# Urukul_FPGA.net
KiCad netlist of a schematic drawn in Altium Designer
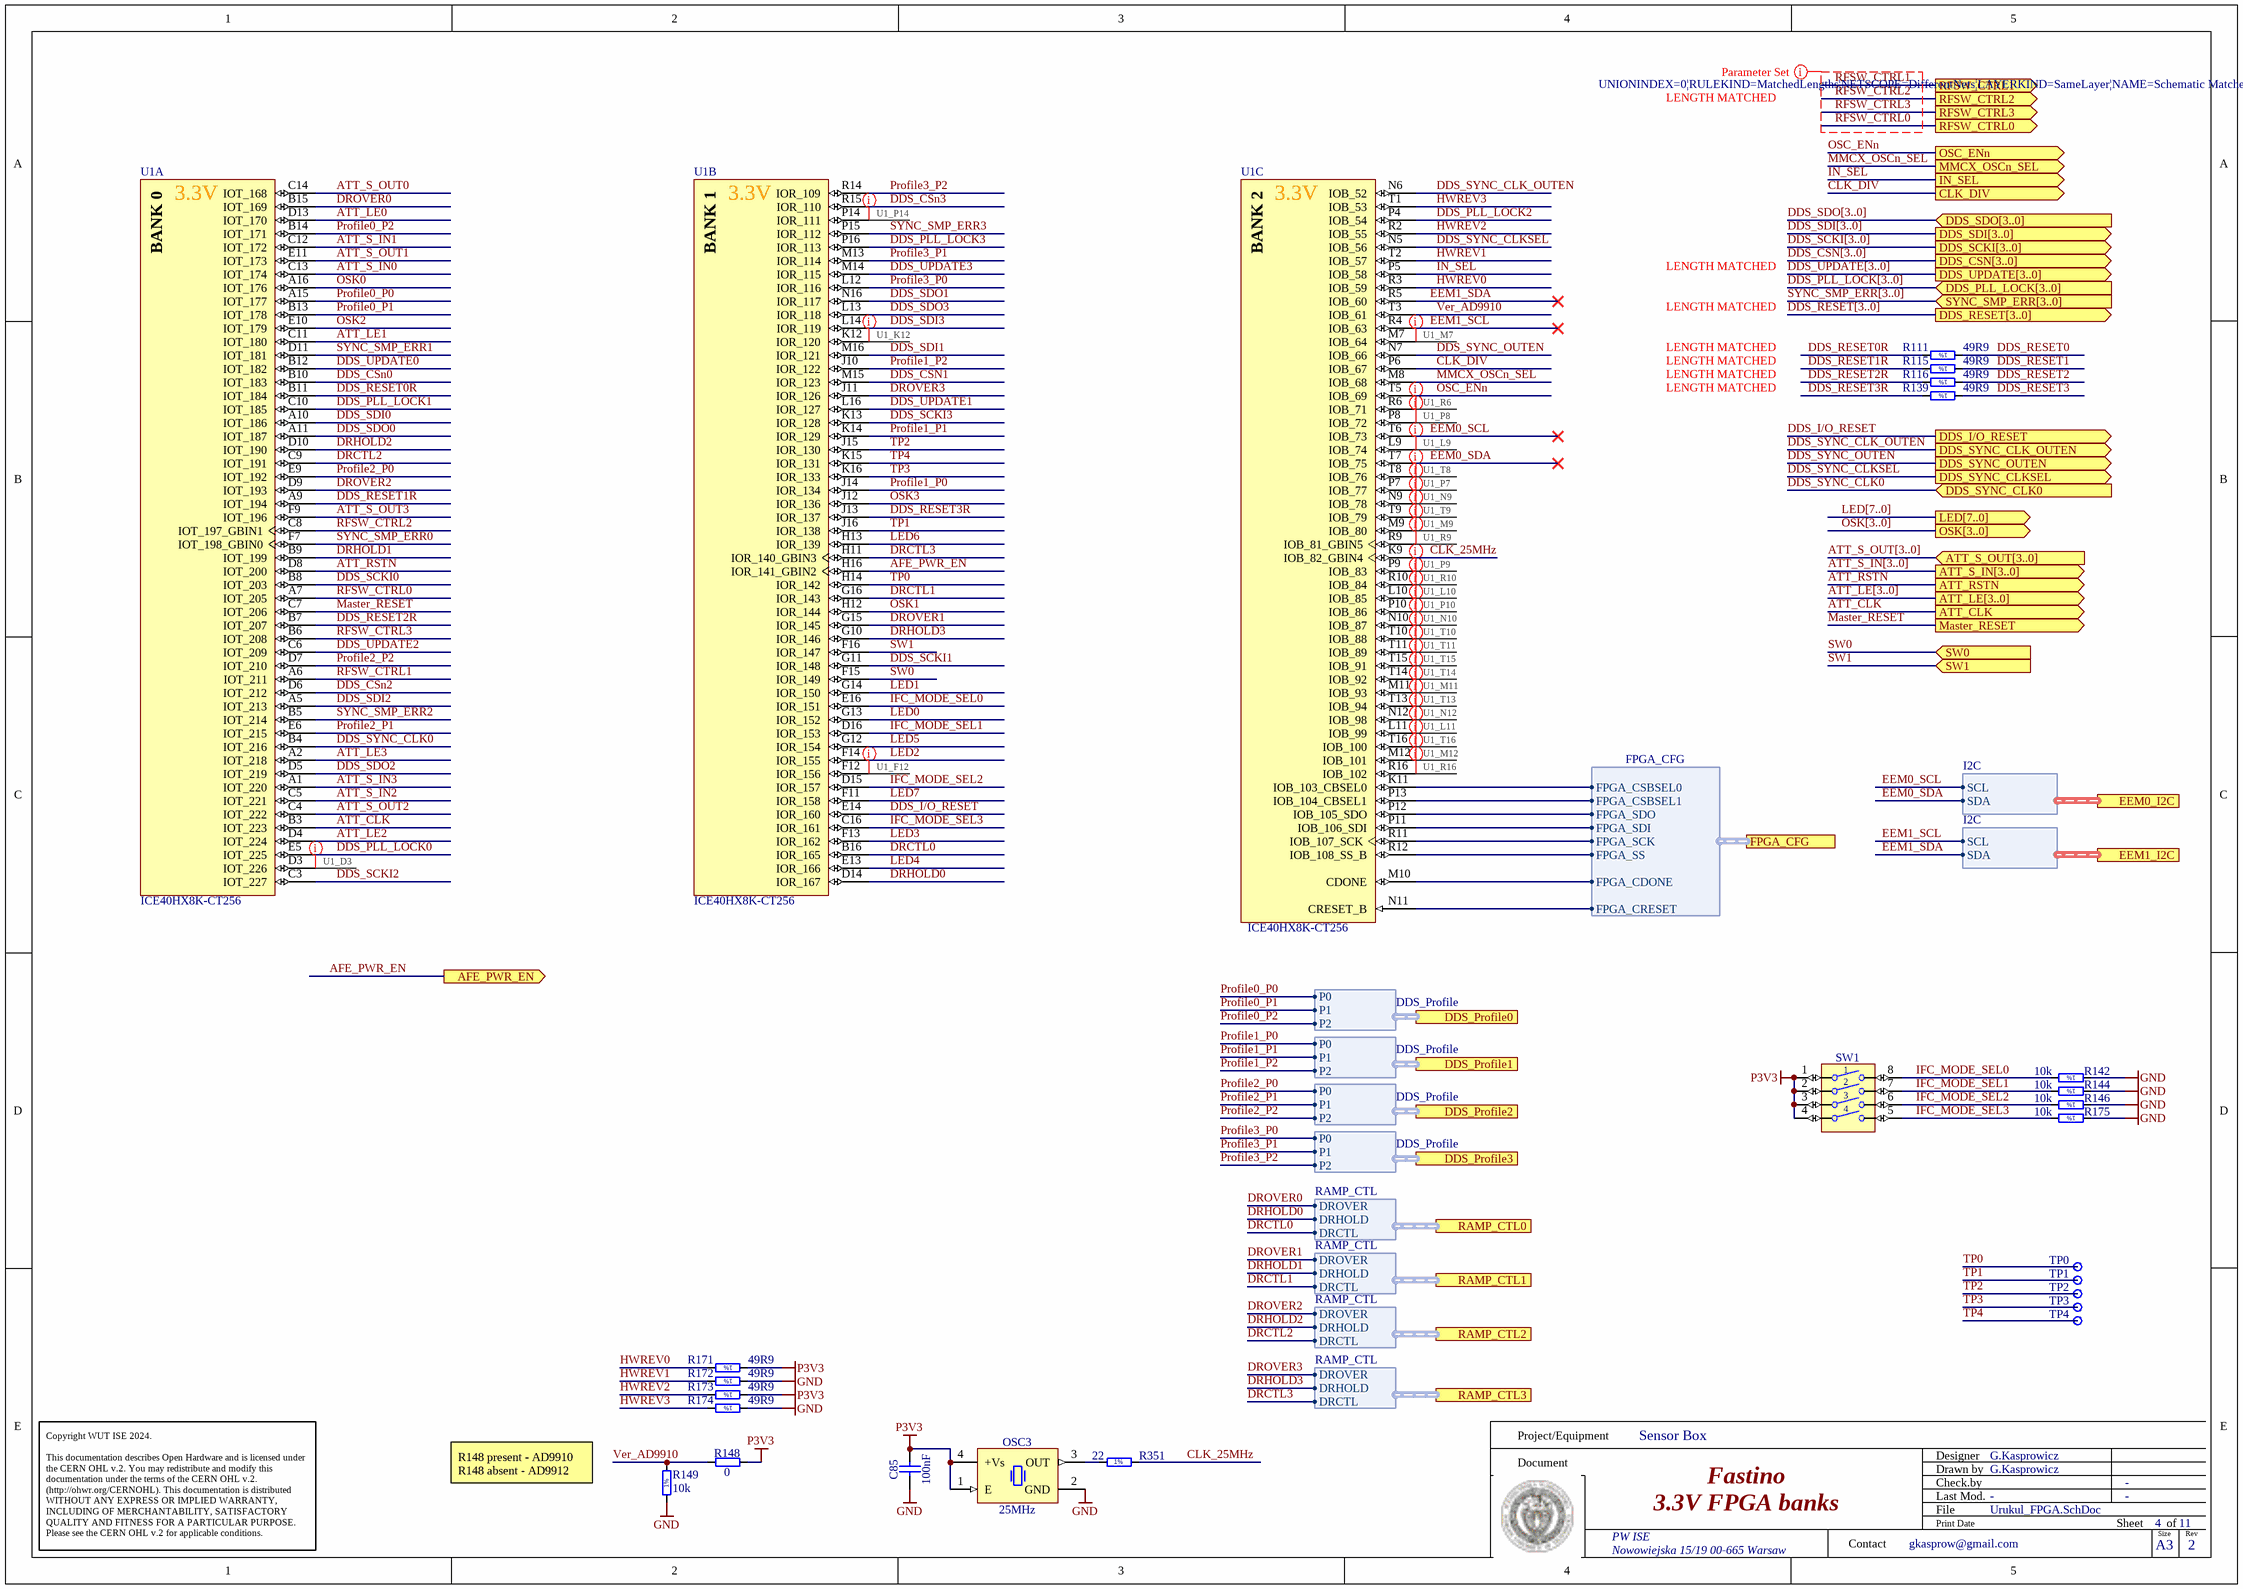
[diagram p0: Urukul_FPGA.SchDoc]

(export (version "E")
  (design (tool "Eeschema 10.0.6"))
  (components
    (comp (ref "C85")
      (value "100nF")
      (footprint "CAPC1005X55N")
      (description "Non-polarised capacitor")
      (fields
        (field (name "PART NUMBER") "CC0402_100NF_16V_10%_X5R")
        (field (name "VOLTAGE") "16V")
        (field (name "AUTHOR") "CERN DEM JLC")
      )
      (libsource (lib "Capacitors") (part "Capacitor - non polarized"))
    )
    (comp (ref "OSC3")
      (value "25MHz")
      (footprint "OSC_IQD_CFPS-39")
      (description "Oscillator 4 pins 1=E 2=GND 3=OUT 4=+Vs")
      (fields
        (field (name "PART NUMBER") "OSC_25MHZ_IQD_LFSPXO025165")
        (field (name "MANUFACTURER") "IQD FREQUENCY PRODUCTS")
        (field (name "AUTHOR") "CERN DEM JLC")
      )
      (libsource (lib "ICs And Semiconductors") (part "Oscillator 1E 2GND 3OUT 4Vs"))
    )
    (comp (ref "R111")
      (value "49R9")
      (footprint "RESC1005X40N")
      (description "Resistor - 1%")
      (fields
        (field (name "PART NUMBER") "R0402_49R9_1%_0.0625W_100PPM")
        (field (name "POWER") "0.0625W")
        (field (name "AUTHOR") "CERN DEM JLC")
      )
      (libsource (lib "Resistors") (part "Resistor - 1%"))
    )
    (comp (ref "R115")
      (value "49R9")
      (footprint "RESC1005X40N")
      (description "Resistor - 1%")
      (fields
        (field (name "PART NUMBER") "R0402_49R9_1%_0.0625W_100PPM")
        (field (name "POWER") "0.0625W")
        (field (name "AUTHOR") "CERN DEM JLC")
      )
      (libsource (lib "Resistors") (part "Resistor - 1%"))
    )
    (comp (ref "R116")
      (value "49R9")
      (footprint "RESC1005X40N")
      (description "Resistor - 1%")
      (fields
        (field (name "PART NUMBER") "R0402_49R9_1%_0.0625W_100PPM")
        (field (name "POWER") "0.0625W")
        (field (name "AUTHOR") "CERN DEM JLC")
      )
      (libsource (lib "Resistors") (part "Resistor - 1%"))
    )
    (comp (ref "R139")
      (value "49R9")
      (footprint "RESC1005X40N")
      (description "Resistor - 1%")
      (fields
        (field (name "PART NUMBER") "R0402_49R9_1%_0.0625W_100PPM")
        (field (name "POWER") "0.0625W")
        (field (name "AUTHOR") "CERN DEM JLC")
      )
      (libsource (lib "Resistors") (part "Resistor - 1%"))
    )
    (comp (ref "R142")
      (value "10k")
      (footprint "RESC1005X40N")
      (description "Resistor - 1%")
      (fields
        (field (name "PART NUMBER") "R0402_10K_1%_0.0625W_100PPM")
        (field (name "POWER") "0.0625W")
        (field (name "AUTHOR") "CERN DEM JLC")
      )
      (libsource (lib "Resistors") (part "Resistor - 1%"))
    )
    (comp (ref "R144")
      (value "10k")
      (footprint "RESC1005X40N")
      (description "Resistor - 1%")
      (fields
        (field (name "PART NUMBER") "R0402_10K_1%_0.0625W_100PPM")
        (field (name "POWER") "0.0625W")
        (field (name "AUTHOR") "CERN DEM JLC")
      )
      (libsource (lib "Resistors") (part "Resistor - 1%"))
    )
    (comp (ref "R146")
      (value "10k")
      (footprint "RESC1005X40N")
      (description "Resistor - 1%")
      (fields
        (field (name "PART NUMBER") "R0402_10K_1%_0.0625W_100PPM")
        (field (name "POWER") "0.0625W")
        (field (name "AUTHOR") "CERN DEM JLC")
      )
      (libsource (lib "Resistors") (part "Resistor - 1%"))
    )
    (comp (ref "R148")
      (value "0")
      (footprint "RESC1005X40N")
      (description "Resistor")
      (fields
        (field (name "PART NUMBER") "R0402_0R_JUMPER")
        (field (name "MANUFACTURER") "GENERIC")
        (field (name "AUTHOR") "CERN DEM JLC")
      )
      (libsource (lib "Resistors") (part "Resistor"))
    )
    (comp (ref "R149")
      (value "10k")
      (footprint "RESC1005X40N")
      (description "Resistor - 1%")
      (fields
        (field (name "PART NUMBER") "R0402_10K_1%_0.0625W_100PPM")
        (field (name "POWER") "0.0625W")
        (field (name "AUTHOR") "CERN DEM JLC")
      )
      (libsource (lib "Resistors") (part "Resistor - 1%"))
    )
    (comp (ref "R171")
      (value "49R9")
      (footprint "RESC1005X40N")
      (description "Resistor - 1%")
      (fields
        (field (name "PART NUMBER") "R0402_49R9_1%_0.0625W_100PPM")
        (field (name "POWER") "0.0625W")
        (field (name "AUTHOR") "CERN DEM JLC")
      )
      (libsource (lib "Resistors") (part "Resistor - 1%"))
    )
    (comp (ref "R172")
      (value "49R9")
      (footprint "RESC1005X40N")
      (description "Resistor - 1%")
      (fields
        (field (name "PART NUMBER") "R0402_49R9_1%_0.0625W_100PPM")
        (field (name "POWER") "0.0625W")
        (field (name "AUTHOR") "CERN DEM JLC")
      )
      (libsource (lib "Resistors") (part "Resistor - 1%"))
    )
    (comp (ref "R173")
      (value "49R9")
      (footprint "RESC1005X40N")
      (description "Resistor - 1%")
      (fields
        (field (name "PART NUMBER") "R0402_49R9_1%_0.0625W_100PPM")
        (field (name "POWER") "0.0625W")
        (field (name "AUTHOR") "CERN DEM JLC")
      )
      (libsource (lib "Resistors") (part "Resistor - 1%"))
    )
    (comp (ref "R174")
      (value "49R9")
      (footprint "RESC1005X40N")
      (description "Resistor - 1%")
      (fields
        (field (name "PART NUMBER") "R0402_49R9_1%_0.0625W_100PPM")
        (field (name "POWER") "0.0625W")
        (field (name "AUTHOR") "CERN DEM JLC")
      )
      (libsource (lib "Resistors") (part "Resistor - 1%"))
    )
    (comp (ref "R175")
      (value "10k")
      (footprint "RESC1005X40N")
      (description "Resistor - 1%")
      (fields
        (field (name "PART NUMBER") "R0402_10K_1%_0.0625W_100PPM")
        (field (name "POWER") "0.0625W")
        (field (name "AUTHOR") "CERN DEM JLC")
      )
      (libsource (lib "Resistors") (part "Resistor - 1%"))
    )
    (comp (ref "R351")
      (value "22")
      (footprint "RESC1005X40N")
      (description "Resistor - 1%")
      (fields
        (field (name "PART NUMBER") "R0402_22R_1%_0.0625W_100PPM")
        (field (name "POWER") "0.0625W")
        (field (name "AUTHOR") "CERN DEM JLC")
      )
      (libsource (lib "Resistors") (part "Resistor - 1%"))
    )
    (comp (ref "SW1")
      (value "Switch")
      (footprint "SW_TYCO_1571983-4")
      (description "4 Ways SPST DIP Switch")
      (fields
        (field (name "PART NUMBER") "SW_TYCO_1571983-4")
        (field (name "MANUFACTURER") "TYCO")
        (field (name "AUTHOR") "CERN DEM JLC")
      )
      (libsource (lib "Eletro-mechanical") (part "SW 4x SPST DIP Switch"))
    )
    (comp (ref "TP0")
      (value "Test Point")
      (footprint "TPS127")
      (fields (field (name "PART NUMBER") "SMD_PAD_1.27X1.27MM") (field (name "AUTHOR") "CERN DEM JLC"))
      (libsource (lib "Eletro-mechanical") (part "Test Point"))
    )
    (comp (ref "TP1")
      (value "Test Point")
      (footprint "TPS127")
      (fields (field (name "PART NUMBER") "SMD_PAD_1.27X1.27MM") (field (name "AUTHOR") "CERN DEM JLC"))
      (libsource (lib "Eletro-mechanical") (part "Test Point"))
    )
    (comp (ref "TP2")
      (value "Test Point")
      (footprint "TPS127")
      (fields (field (name "PART NUMBER") "SMD_PAD_1.27X1.27MM") (field (name "AUTHOR") "CERN DEM JLC"))
      (libsource (lib "Eletro-mechanical") (part "Test Point"))
    )
    (comp (ref "TP3")
      (value "Test Point")
      (footprint "TPS127")
      (fields (field (name "PART NUMBER") "SMD_PAD_1.27X1.27MM") (field (name "AUTHOR") "CERN DEM JLC"))
      (libsource (lib "Eletro-mechanical") (part "Test Point"))
    )
    (comp (ref "TP4")
      (value "Test Point")
      (footprint "TPS127")
      (fields (field (name "PART NUMBER") "SMD_PAD_1.27X1.27MM") (field (name "AUTHOR") "CERN DEM JLC"))
      (libsource (lib "Eletro-mechanical") (part "Test Point"))
    )
    (comp (ref "U1")
      (value "ICE40HX8K-CT256")
      (footprint "LATC-caBGA-256")
      (fields (field (name "MANUFACTURER") "Lattice Semiconductor"))
      (libsource (lib "Altium Content Vault") (part "LATC-HX8K-caBGA-256"))
    )
  )
  (nets
    (net (code "8") (name "/AFE_PWR_EN") (class "Default")
      (node (ref "U1") (pin "H16") (pinfunction "IOR_141_GBIN2_H16") (pintype "bidirectional"))
    )
    (net (code "9") (name "/ATT_CLK") (class "Default")
      (node (ref "U1") (pin "B3") (pinfunction "IOT_223_B3") (pintype "bidirectional"))
    )
    (net (code "10") (name "/ATT_LE0") (class "Default")
      (node (ref "U1") (pin "D13") (pinfunction "IOT_170_D13") (pintype "bidirectional"))
    )
    (net (code "11") (name "/ATT_LE1") (class "Default")
      (node (ref "U1") (pin "C11") (pinfunction "IOT_180_C11") (pintype "bidirectional"))
    )
    (net (code "12") (name "/ATT_LE2") (class "Default")
      (node (ref "U1") (pin "D4") (pinfunction "IOT_224_D4") (pintype "bidirectional"))
    )
    (net (code "13") (name "/ATT_LE3") (class "Default")
      (node (ref "U1") (pin "A2") (pinfunction "IOT_218_A2") (pintype "bidirectional"))
    )
    (net (code "15") (name "/ATT_RSTN") (class "Default")
      (node (ref "U1") (pin "D8") (pinfunction "IOT_200_D8") (pintype "bidirectional"))
    )
    (net (code "16") (name "/ATT_S_IN0") (class "Default")
      (node (ref "U1") (pin "C13") (pinfunction "IOT_174_C13") (pintype "bidirectional"))
    )
    (net (code "17") (name "/ATT_S_IN1") (class "Default")
      (node (ref "U1") (pin "C12") (pinfunction "IOT_172_C12") (pintype "bidirectional"))
    )
    (net (code "18") (name "/ATT_S_IN2") (class "Default")
      (node (ref "U1") (pin "C5") (pinfunction "IOT_221_C5") (pintype "bidirectional"))
    )
    (net (code "19") (name "/ATT_S_IN3") (class "Default")
      (node (ref "U1") (pin "A1") (pinfunction "IOT_220_A1") (pintype "bidirectional"))
    )
    (net (code "21") (name "/ATT_S_OUT0") (class "Default")
      (node (ref "U1") (pin "C14") (pinfunction "IOT_168_C14") (pintype "bidirectional"))
    )
    (net (code "22") (name "/ATT_S_OUT1") (class "Default")
      (node (ref "U1") (pin "E11") (pinfunction "IOT_173_E11") (pintype "bidirectional"))
    )
    (net (code "23") (name "/ATT_S_OUT2") (class "Default")
      (node (ref "U1") (pin "C4") (pinfunction "IOT_222_C4") (pintype "bidirectional"))
    )
    (net (code "24") (name "/ATT_S_OUT3") (class "Default")
      (node (ref "U1") (pin "F9") (pinfunction "IOT_196_F9") (pintype "bidirectional"))
    )
    (net (code "26") (name "/CLK_25MHz") (class "Default")
      (node (ref "R351") (pin "2") (pinfunction "2_2") (pintype "passive"))
      (node (ref "U1") (pin "K9") (pinfunction "IOB_82_GBIN4_K9") (pintype "bidirectional"))
    )
    (net (code "27") (name "/CLK_DIV") (class "Default")
      (node (ref "U1") (pin "P6") (pinfunction "IOB_67_P6") (pintype "bidirectional"))
    )
    (net (code "28") (name "/DDS_CSN1") (class "Default")
      (node (ref "U1") (pin "M15") (pinfunction "IOR_123_M15") (pintype "bidirectional"))
    )
    (net (code "30") (name "/DDS_CSn0") (class "Default")
      (node (ref "U1") (pin "B10") (pinfunction "IOT_183_B10") (pintype "bidirectional"))
    )
    (net (code "31") (name "/DDS_CSn2") (class "Default")
      (node (ref "U1") (pin "D6") (pinfunction "IOT_212_D6") (pintype "bidirectional"))
    )
    (net (code "32") (name "/DDS_CSn3") (class "Default")
      (node (ref "U1") (pin "R15") (pinfunction "IOR_110_R15") (pintype "bidirectional"))
    )
    (net (code "33") (name "/DDS_I{slash}O_RESET") (class "Default")
      (node (ref "U1") (pin "E14") (pinfunction "IOR_160_E14") (pintype "bidirectional"))
    )
    (net (code "34") (name "/DDS_PLL_LOCK0") (class "Default")
      (node (ref "U1") (pin "E5") (pinfunction "IOT_225_E5") (pintype "bidirectional"))
    )
    (net (code "35") (name "/DDS_PLL_LOCK1") (class "Default")
      (node (ref "U1") (pin "C10") (pinfunction "IOT_185_C10") (pintype "bidirectional"))
    )
    (net (code "36") (name "/DDS_PLL_LOCK2") (class "Default")
      (node (ref "U1") (pin "P4") (pinfunction "IOB_54_P4") (pintype "bidirectional"))
    )
    (net (code "37") (name "/DDS_PLL_LOCK3") (class "Default")
      (node (ref "U1") (pin "P16") (pinfunction "IOR_113_P16") (pintype "bidirectional"))
    )
    (net (code "39") (name "/DDS_RESET0") (class "Default")
      (node (ref "R111") (pin "1") (pinfunction "1_1") (pintype "passive"))
    )
    (net (code "40") (name "/DDS_RESET0R") (class "Default")
      (node (ref "R111") (pin "2") (pinfunction "2_2") (pintype "passive"))
      (node (ref "U1") (pin "B11") (pinfunction "IOT_184_B11") (pintype "bidirectional"))
    )
    (net (code "41") (name "/DDS_RESET1") (class "Default")
      (node (ref "R115") (pin "1") (pinfunction "1_1") (pintype "passive"))
    )
    (net (code "42") (name "/DDS_RESET1R") (class "Default")
      (node (ref "R115") (pin "2") (pinfunction "2_2") (pintype "passive"))
      (node (ref "U1") (pin "A9") (pinfunction "IOT_194_A9") (pintype "bidirectional"))
    )
    (net (code "43") (name "/DDS_RESET2") (class "Default")
      (node (ref "R116") (pin "1") (pinfunction "1_1") (pintype "passive"))
    )
    (net (code "44") (name "/DDS_RESET2R") (class "Default")
      (node (ref "R116") (pin "2") (pinfunction "2_2") (pintype "passive"))
      (node (ref "U1") (pin "B7") (pinfunction "IOT_207_B7") (pintype "bidirectional"))
    )
    (net (code "45") (name "/DDS_RESET3") (class "Default")
      (node (ref "R139") (pin "1") (pinfunction "1_1") (pintype "passive"))
    )
    (net (code "46") (name "/DDS_RESET3R") (class "Default")
      (node (ref "R139") (pin "2") (pinfunction "2_2") (pintype "passive"))
      (node (ref "U1") (pin "J13") (pinfunction "IOR_137_J13") (pintype "bidirectional"))
    )
    (net (code "48") (name "/DDS_SCKI0") (class "Default")
      (node (ref "U1") (pin "B8") (pinfunction "IOT_203_B8") (pintype "bidirectional"))
    )
    (net (code "49") (name "/DDS_SCKI1") (class "Default")
      (node (ref "U1") (pin "G11") (pinfunction "IOR_148_G11") (pintype "bidirectional"))
    )
    (net (code "50") (name "/DDS_SCKI2") (class "Default")
      (node (ref "U1") (pin "C3") (pinfunction "IOT_227_C3") (pintype "bidirectional"))
    )
    (net (code "51") (name "/DDS_SCKI3") (class "Default")
      (node (ref "U1") (pin "K13") (pinfunction "IOR_128_K13") (pintype "bidirectional"))
    )
    (net (code "53") (name "/DDS_SDI0") (class "Default")
      (node (ref "U1") (pin "A10") (pinfunction "IOT_186_A10") (pintype "bidirectional"))
    )
    (net (code "54") (name "/DDS_SDI1") (class "Default")
      (node (ref "U1") (pin "M16") (pinfunction "IOR_121_M16") (pintype "bidirectional"))
    )
    (net (code "55") (name "/DDS_SDI2") (class "Default")
      (node (ref "U1") (pin "A5") (pinfunction "IOT_213_A5") (pintype "bidirectional"))
    )
    (net (code "56") (name "/DDS_SDI3") (class "Default")
      (node (ref "U1") (pin "L14") (pinfunction "IOR_119_L14") (pintype "bidirectional"))
    )
    (net (code "58") (name "/DDS_SDO0") (class "Default")
      (node (ref "U1") (pin "A11") (pinfunction "IOT_187_A11") (pintype "bidirectional"))
    )
    (net (code "59") (name "/DDS_SDO1") (class "Default")
      (node (ref "U1") (pin "N16") (pinfunction "IOR_117_N16") (pintype "bidirectional"))
    )
    (net (code "60") (name "/DDS_SDO2") (class "Default")
      (node (ref "U1") (pin "D5") (pinfunction "IOT_219_D5") (pintype "bidirectional"))
    )
    (net (code "61") (name "/DDS_SDO3") (class "Default")
      (node (ref "U1") (pin "L13") (pinfunction "IOR_118_L13") (pintype "bidirectional"))
    )
    (net (code "63") (name "/DDS_SYNC_CLK0") (class "Default")
      (node (ref "U1") (pin "B4") (pinfunction "IOT_216_B4") (pintype "bidirectional"))
    )
    (net (code "64") (name "/DDS_SYNC_CLKSEL") (class "Default")
      (node (ref "U1") (pin "N5") (pinfunction "IOB_56_N5") (pintype "bidirectional"))
    )
    (net (code "65") (name "/DDS_SYNC_CLK_OUTEN") (class "Default")
      (node (ref "U1") (pin "N6") (pinfunction "IOB_52_N6") (pintype "bidirectional"))
    )
    (net (code "66") (name "/DDS_SYNC_OUTEN") (class "Default")
      (node (ref "U1") (pin "N7") (pinfunction "IOB_66_N7") (pintype "bidirectional"))
    )
    (net (code "67") (name "/DDS_UPDATE0") (class "Default")
      (node (ref "U1") (pin "B12") (pinfunction "IOT_182_B12") (pintype "bidirectional"))
    )
    (net (code "68") (name "/DDS_UPDATE1") (class "Default")
      (node (ref "U1") (pin "L16") (pinfunction "IOR_127_L16") (pintype "bidirectional"))
    )
    (net (code "69") (name "/DDS_UPDATE2") (class "Default")
      (node (ref "U1") (pin "C6") (pinfunction "IOT_209_C6") (pintype "bidirectional"))
    )
    (net (code "70") (name "/DDS_UPDATE3") (class "Default")
      (node (ref "U1") (pin "M14") (pinfunction "IOR_115_M14") (pintype "bidirectional"))
    )
    (net (code "72") (name "/DRCTL0") (class "Default")
      (node (ref "U1") (pin "B16") (pinfunction "IOR_165_B16") (pintype "bidirectional"))
    )
    (net (code "73") (name "/DRCTL1") (class "Default")
      (node (ref "U1") (pin "G16") (pinfunction "IOR_143_G16") (pintype "bidirectional"))
    )
    (net (code "74") (name "/DRCTL2") (class "Default")
      (node (ref "U1") (pin "C9") (pinfunction "IOT_191_C9") (pintype "bidirectional"))
    )
    (net (code "75") (name "/DRCTL3") (class "Default")
      (node (ref "U1") (pin "H11") (pinfunction "IOR_140_GBIN3_H11") (pintype "bidirectional"))
    )
    (net (code "76") (name "/DRHOLD0") (class "Default")
      (node (ref "U1") (pin "D14") (pinfunction "IOR_167_D14") (pintype "bidirectional"))
    )
    (net (code "77") (name "/DRHOLD1") (class "Default")
      (node (ref "U1") (pin "B9") (pinfunction "IOT_199_B9") (pintype "bidirectional"))
    )
    (net (code "78") (name "/DRHOLD2") (class "Default")
      (node (ref "U1") (pin "D10") (pinfunction "IOT_190_D10") (pintype "bidirectional"))
    )
    (net (code "79") (name "/DRHOLD3") (class "Default")
      (node (ref "U1") (pin "G10") (pinfunction "IOR_146_G10") (pintype "bidirectional"))
    )
    (net (code "80") (name "/DROVER0") (class "Default")
      (node (ref "U1") (pin "B15") (pinfunction "IOT_169_B15") (pintype "bidirectional"))
    )
    (net (code "81") (name "/DROVER1") (class "Default")
      (node (ref "U1") (pin "G15") (pinfunction "IOR_145_G15") (pintype "bidirectional"))
    )
    (net (code "82") (name "/DROVER2") (class "Default")
      (node (ref "U1") (pin "D9") (pinfunction "IOT_193_D9") (pintype "bidirectional"))
    )
    (net (code "83") (name "/DROVER3") (class "Default")
      (node (ref "U1") (pin "J11") (pinfunction "IOR_126_J11") (pintype "bidirectional"))
    )
    (net (code "84") (name "/EEM0_SCL") (class "Default")
      (node (ref "U1") (pin "T6") (pinfunction "IOB_73_T6") (pintype "bidirectional"))
    )
    (net (code "85") (name "/EEM0_SDA") (class "Default")
      (node (ref "U1") (pin "T7") (pinfunction "IOB_75_T7") (pintype "bidirectional"))
    )
    (net (code "86") (name "/EEM1_SCL") (class "Default")
      (node (ref "U1") (pin "R4") (pinfunction "IOB_63_R4") (pintype "bidirectional"))
    )
    (net (code "87") (name "/EEM1_SDA") (class "Default")
      (node (ref "U1") (pin "R5") (pinfunction "IOB_60_R5") (pintype "bidirectional"))
    )
    (net (code "88") (name "/FPGA_CDONE") (class "Default")
      (node (ref "U1") (pin "M10") (pinfunction "CDONE_M10") (pintype "bidirectional"))
    )
    (net (code "89") (name "/FPGA_CRESET") (class "Default")
      (node (ref "U1") (pin "N11") (pinfunction "CRESET_B_N11") (pintype "input"))
    )
    (net (code "90") (name "/FPGA_CSBSEL0") (class "Default")
      (node (ref "U1") (pin "K11") (pinfunction "IOB_103_CBSEL0_K11") (pintype "bidirectional"))
    )
    (net (code "91") (name "/FPGA_CSBSEL1") (class "Default")
      (node (ref "U1") (pin "P13") (pinfunction "IOB_104_CBSEL1_P13") (pintype "bidirectional"))
    )
    (net (code "92") (name "/FPGA_SCK") (class "Default")
      (node (ref "U1") (pin "R11") (pinfunction "IOB_107_SCK_R11") (pintype "bidirectional"))
    )
    (net (code "93") (name "/FPGA_SDI") (class "Default")
      (node (ref "U1") (pin "P11") (pinfunction "IOB_106_SDI_P11") (pintype "bidirectional"))
    )
    (net (code "94") (name "/FPGA_SDO") (class "Default")
      (node (ref "U1") (pin "P12") (pinfunction "IOB_105_SDO_P12") (pintype "bidirectional"))
    )
    (net (code "95") (name "/FPGA_SS") (class "Default")
      (node (ref "U1") (pin "R12") (pinfunction "IOB_108_SS_B_R12") (pintype "bidirectional"))
    )
    (net (code "96") (name "/HWREV0") (class "Default")
      (node (ref "R171") (pin "2") (pinfunction "2_2") (pintype "passive"))
      (node (ref "U1") (pin "R3") (pinfunction "IOB_59_R3") (pintype "bidirectional"))
    )
    (net (code "97") (name "/HWREV1") (class "Default")
      (node (ref "R172") (pin "2") (pinfunction "2_2") (pintype "passive"))
      (node (ref "U1") (pin "T2") (pinfunction "IOB_57_T2") (pintype "bidirectional"))
    )
    (net (code "98") (name "/HWREV2") (class "Default")
      (node (ref "R173") (pin "2") (pinfunction "2_2") (pintype "passive"))
      (node (ref "U1") (pin "R2") (pinfunction "IOB_55_R2") (pintype "bidirectional"))
    )
    (net (code "99") (name "/HWREV3") (class "Default")
      (node (ref "R174") (pin "2") (pinfunction "2_2") (pintype "passive"))
      (node (ref "U1") (pin "T1") (pinfunction "IOB_53_T1") (pintype "bidirectional"))
    )
    (net (code "100") (name "/IFC_MODE_SEL0") (class "Default")
      (node (ref "R142") (pin "2") (pinfunction "2_2") (pintype "passive"))
      (node (ref "SW1") (pin "8") (pinfunction "8_8") (pintype "bidirectional"))
      (node (ref "U1") (pin "E16") (pinfunction "IOR_151_E16") (pintype "bidirectional"))
    )
    (net (code "101") (name "/IFC_MODE_SEL1") (class "Default")
      (node (ref "R144") (pin "2") (pinfunction "2_2") (pintype "passive"))
      (node (ref "SW1") (pin "7") (pinfunction "7_7") (pintype "bidirectional"))
      (node (ref "U1") (pin "D16") (pinfunction "IOR_153_D16") (pintype "bidirectional"))
    )
    (net (code "102") (name "/IFC_MODE_SEL2") (class "Default")
      (node (ref "R146") (pin "2") (pinfunction "2_2") (pintype "passive"))
      (node (ref "SW1") (pin "6") (pinfunction "6_6") (pintype "bidirectional"))
      (node (ref "U1") (pin "D15") (pinfunction "IOR_157_D15") (pintype "bidirectional"))
    )
    (net (code "103") (name "/IFC_MODE_SEL3") (class "Default")
      (node (ref "R175") (pin "2") (pinfunction "2_2") (pintype "passive"))
      (node (ref "SW1") (pin "5") (pinfunction "5_5") (pintype "bidirectional"))
      (node (ref "U1") (pin "C16") (pinfunction "IOR_161_C16") (pintype "bidirectional"))
    )
    (net (code "104") (name "/IN_SEL") (class "Default")
      (node (ref "U1") (pin "P5") (pinfunction "IOB_58_P5") (pintype "bidirectional"))
    )
    (net (code "105") (name "/LED0") (class "Default")
      (node (ref "U1") (pin "G13") (pinfunction "IOR_152_G13") (pintype "bidirectional"))
    )
    (net (code "106") (name "/LED1") (class "Default")
      (node (ref "U1") (pin "G14") (pinfunction "IOR_150_G14") (pintype "bidirectional"))
    )
    (net (code "107") (name "/LED2") (class "Default")
      (node (ref "U1") (pin "F14") (pinfunction "IOR_155_F14") (pintype "bidirectional"))
    )
    (net (code "108") (name "/LED3") (class "Default")
      (node (ref "U1") (pin "F13") (pinfunction "IOR_162_F13") (pintype "bidirectional"))
    )
    (net (code "109") (name "/LED4") (class "Default")
      (node (ref "U1") (pin "E13") (pinfunction "IOR_166_E13") (pintype "bidirectional"))
    )
    (net (code "110") (name "/LED5") (class "Default")
      (node (ref "U1") (pin "G12") (pinfunction "IOR_154_G12") (pintype "bidirectional"))
    )
    (net (code "111") (name "/LED6") (class "Default")
      (node (ref "U1") (pin "H13") (pinfunction "IOR_139_H13") (pintype "bidirectional"))
    )
    (net (code "112") (name "/LED7") (class "Default")
      (node (ref "U1") (pin "F11") (pinfunction "IOR_158_F11") (pintype "bidirectional"))
    )
    (net (code "114") (name "/MMCX_OSCn_SEL") (class "Default")
      (node (ref "U1") (pin "M8") (pinfunction "IOB_68_M8") (pintype "bidirectional"))
    )
    (net (code "115") (name "/Master_RESET") (class "Default")
      (node (ref "U1") (pin "C7") (pinfunction "IOT_206_C7") (pintype "bidirectional"))
    )
    (net (code "116") (name "/OSC_ENn") (class "Default")
      (node (ref "U1") (pin "T5") (pinfunction "IOB_69_T5") (pintype "bidirectional"))
    )
    (net (code "117") (name "/OSK0") (class "Default")
      (node (ref "U1") (pin "A16") (pinfunction "IOT_176_A16") (pintype "bidirectional"))
    )
    (net (code "118") (name "/OSK1") (class "Default")
      (node (ref "U1") (pin "H12") (pinfunction "IOR_144_H12") (pintype "bidirectional"))
    )
    (net (code "119") (name "/OSK2") (class "Default")
      (node (ref "U1") (pin "E10") (pinfunction "IOT_179_E10") (pintype "bidirectional"))
    )
    (net (code "120") (name "/OSK3") (class "Default")
      (node (ref "U1") (pin "J12") (pinfunction "IOR_136_J12") (pintype "bidirectional"))
    )
    (net (code "122") (name "/Profile0_P0") (class "Default")
      (node (ref "U1") (pin "A15") (pinfunction "IOT_177_A15") (pintype "bidirectional"))
    )
    (net (code "123") (name "/Profile0_P1") (class "Default")
      (node (ref "U1") (pin "B13") (pinfunction "IOT_178_B13") (pintype "bidirectional"))
    )
    (net (code "124") (name "/Profile0_P2") (class "Default")
      (node (ref "U1") (pin "B14") (pinfunction "IOT_171_B14") (pintype "bidirectional"))
    )
    (net (code "125") (name "/Profile1_P0") (class "Default")
      (node (ref "U1") (pin "J14") (pinfunction "IOR_134_J14") (pintype "bidirectional"))
    )
    (net (code "126") (name "/Profile1_P1") (class "Default")
      (node (ref "U1") (pin "K14") (pinfunction "IOR_129_K14") (pintype "bidirectional"))
    )
    (net (code "127") (name "/Profile1_P2") (class "Default")
      (node (ref "U1") (pin "J10") (pinfunction "IOR_122_J10") (pintype "bidirectional"))
    )
    (net (code "128") (name "/Profile2_P0") (class "Default")
      (node (ref "U1") (pin "E9") (pinfunction "IOT_192_E9") (pintype "bidirectional"))
    )
    (net (code "129") (name "/Profile2_P1") (class "Default")
      (node (ref "U1") (pin "E6") (pinfunction "IOT_215_E6") (pintype "bidirectional"))
    )
    (net (code "130") (name "/Profile2_P2") (class "Default")
      (node (ref "U1") (pin "D7") (pinfunction "IOT_210_D7") (pintype "bidirectional"))
    )
    (net (code "131") (name "/Profile3_P0") (class "Default")
      (node (ref "U1") (pin "L12") (pinfunction "IOR_116_L12") (pintype "bidirectional"))
    )
    (net (code "132") (name "/Profile3_P1") (class "Default")
      (node (ref "U1") (pin "M13") (pinfunction "IOR_114_M13") (pintype "bidirectional"))
    )
    (net (code "133") (name "/Profile3_P2") (class "Default")
      (node (ref "U1") (pin "R14") (pinfunction "IOR_109_R14") (pintype "bidirectional"))
    )
    (net (code "134") (name "/RFSW_CTRL0") (class "Default")
      (node (ref "U1") (pin "A7") (pinfunction "IOT_205_A7") (pintype "bidirectional"))
    )
    (net (code "135") (name "/RFSW_CTRL1") (class "Default")
      (node (ref "U1") (pin "A6") (pinfunction "IOT_211_A6") (pintype "bidirectional"))
    )
    (net (code "136") (name "/RFSW_CTRL2") (class "Default")
      (node (ref "U1") (pin "C8") (pinfunction "IOT_197_GBIN1_C8") (pintype "bidirectional"))
    )
    (net (code "137") (name "/RFSW_CTRL3") (class "Default")
      (node (ref "U1") (pin "B6") (pinfunction "IOT_208_B6") (pintype "bidirectional"))
    )
    (net (code "138") (name "/SW0") (class "Default")
      (node (ref "U1") (pin "F15") (pinfunction "IOR_149_F15") (pintype "bidirectional"))
    )
    (net (code "139") (name "/SW1") (class "Default")
      (node (ref "U1") (pin "F16") (pinfunction "IOR_147_F16") (pintype "bidirectional"))
    )
    (net (code "140") (name "/SYNC_SMP_ERR0") (class "Default")
      (node (ref "U1") (pin "F7") (pinfunction "IOT_198_GBIN0_F7") (pintype "bidirectional"))
    )
    (net (code "141") (name "/SYNC_SMP_ERR1") (class "Default")
      (node (ref "U1") (pin "D11") (pinfunction "IOT_181_D11") (pintype "bidirectional"))
    )
    (net (code "142") (name "/SYNC_SMP_ERR2") (class "Default")
      (node (ref "U1") (pin "B5") (pinfunction "IOT_214_B5") (pintype "bidirectional"))
    )
    (net (code "143") (name "/SYNC_SMP_ERR3") (class "Default")
      (node (ref "U1") (pin "P15") (pinfunction "IOR_112_P15") (pintype "bidirectional"))
    )
    (net (code "145") (name "/TP0") (class "Default")
      (node (ref "TP0") (pin "1") (pinfunction "1_1") (pintype "bidirectional"))
      (node (ref "U1") (pin "H14") (pinfunction "IOR_142_H14") (pintype "bidirectional"))
    )
    (net (code "146") (name "/TP1") (class "Default")
      (node (ref "TP1") (pin "1") (pinfunction "1_1") (pintype "bidirectional"))
      (node (ref "U1") (pin "J16") (pinfunction "IOR_138_J16") (pintype "bidirectional"))
    )
    (net (code "147") (name "/TP2") (class "Default")
      (node (ref "TP2") (pin "1") (pinfunction "1_1") (pintype "bidirectional"))
      (node (ref "U1") (pin "J15") (pinfunction "IOR_130_J15") (pintype "bidirectional"))
    )
    (net (code "148") (name "/TP3") (class "Default")
      (node (ref "TP3") (pin "1") (pinfunction "1_1") (pintype "bidirectional"))
      (node (ref "U1") (pin "K16") (pinfunction "IOR_133_K16") (pintype "bidirectional"))
    )
    (net (code "149") (name "/TP4") (class "Default")
      (node (ref "TP4") (pin "1") (pinfunction "1_1") (pintype "bidirectional"))
      (node (ref "U1") (pin "K15") (pinfunction "IOR_131_K15") (pintype "bidirectional"))
    )
    (net (code "150") (name "/U1_D3") (class "Default")
      (node (ref "U1") (pin "D3") (pinfunction "IOT_226_D3") (pintype "bidirectional"))
    )
    (net (code "151") (name "/U1_F12") (class "Default")
      (node (ref "U1") (pin "F12") (pinfunction "IOR_156_F12") (pintype "bidirectional"))
    )
    (net (code "152") (name "/U1_K12") (class "Default")
      (node (ref "U1") (pin "K12") (pinfunction "IOR_120_K12") (pintype "bidirectional"))
    )
    (net (code "153") (name "/U1_L9") (class "Default")
      (node (ref "U1") (pin "L9") (pinfunction "IOB_74_L9") (pintype "bidirectional"))
    )
    (net (code "154") (name "/U1_L10") (class "Default")
      (node (ref "U1") (pin "L10") (pinfunction "IOB_85_L10") (pintype "bidirectional"))
    )
    (net (code "155") (name "/U1_L11") (class "Default")
      (node (ref "U1") (pin "L11") (pinfunction "IOB_99_L11") (pintype "bidirectional"))
    )
    (net (code "156") (name "/U1_M7") (class "Default")
      (node (ref "U1") (pin "M7") (pinfunction "IOB_64_M7") (pintype "bidirectional"))
    )
    (net (code "157") (name "/U1_M9") (class "Default")
      (node (ref "U1") (pin "M9") (pinfunction "IOB_80_M9") (pintype "bidirectional"))
    )
    (net (code "158") (name "/U1_M11") (class "Default")
      (node (ref "U1") (pin "M11") (pinfunction "IOB_93_M11") (pintype "bidirectional"))
    )
    (net (code "159") (name "/U1_M12") (class "Default")
      (node (ref "U1") (pin "M12") (pinfunction "IOB_101_M12") (pintype "bidirectional"))
    )
    (net (code "160") (name "/U1_N9") (class "Default")
      (node (ref "U1") (pin "N9") (pinfunction "IOB_78_N9") (pintype "bidirectional"))
    )
    (net (code "161") (name "/U1_N10") (class "Default")
      (node (ref "U1") (pin "N10") (pinfunction "IOB_87_N10") (pintype "bidirectional"))
    )
    (net (code "162") (name "/U1_N12") (class "Default")
      (node (ref "U1") (pin "N12") (pinfunction "IOB_98_N12") (pintype "bidirectional"))
    )
    (net (code "163") (name "/U1_P7") (class "Default")
      (node (ref "U1") (pin "P7") (pinfunction "IOB_77_P7") (pintype "bidirectional"))
    )
    (net (code "164") (name "/U1_P8") (class "Default")
      (node (ref "U1") (pin "P8") (pinfunction "IOB_72_P8") (pintype "bidirectional"))
    )
    (net (code "165") (name "/U1_P9") (class "Default")
      (node (ref "U1") (pin "P9") (pinfunction "IOB_83_P9") (pintype "bidirectional"))
    )
    (net (code "166") (name "/U1_P10") (class "Default")
      (node (ref "U1") (pin "P10") (pinfunction "IOB_86_P10") (pintype "bidirectional"))
    )
    (net (code "167") (name "/U1_P14") (class "Default")
      (node (ref "U1") (pin "P14") (pinfunction "IOR_111_P14") (pintype "bidirectional"))
    )
    (net (code "168") (name "/U1_R6") (class "Default")
      (node (ref "U1") (pin "R6") (pinfunction "IOB_71_R6") (pintype "bidirectional"))
    )
    (net (code "169") (name "/U1_R9") (class "Default")
      (node (ref "U1") (pin "R9") (pinfunction "IOB_81_GBIN5_R9") (pintype "bidirectional"))
    )
    (net (code "170") (name "/U1_R10") (class "Default")
      (node (ref "U1") (pin "R10") (pinfunction "IOB_84_R10") (pintype "bidirectional"))
    )
    (net (code "171") (name "/U1_R16") (class "Default")
      (node (ref "U1") (pin "R16") (pinfunction "IOB_102_R16") (pintype "bidirectional"))
    )
    (net (code "172") (name "/U1_T8") (class "Default")
      (node (ref "U1") (pin "T8") (pinfunction "IOB_76_T8") (pintype "bidirectional"))
    )
    (net (code "173") (name "/U1_T9") (class "Default")
      (node (ref "U1") (pin "T9") (pinfunction "IOB_79_T9") (pintype "bidirectional"))
    )
    (net (code "174") (name "/U1_T10") (class "Default")
      (node (ref "U1") (pin "T10") (pinfunction "IOB_88_T10") (pintype "bidirectional"))
    )
    (net (code "175") (name "/U1_T11") (class "Default")
      (node (ref "U1") (pin "T11") (pinfunction "IOB_89_T11") (pintype "bidirectional"))
    )
    (net (code "176") (name "/U1_T13") (class "Default")
      (node (ref "U1") (pin "T13") (pinfunction "IOB_94_T13") (pintype "bidirectional"))
    )
    (net (code "177") (name "/U1_T14") (class "Default")
      (node (ref "U1") (pin "T14") (pinfunction "IOB_92_T14") (pintype "bidirectional"))
    )
    (net (code "178") (name "/U1_T15") (class "Default")
      (node (ref "U1") (pin "T15") (pinfunction "IOB_91_T15") (pintype "bidirectional"))
    )
    (net (code "179") (name "/U1_T16") (class "Default")
      (node (ref "U1") (pin "T16") (pinfunction "IOB_100_T16") (pintype "bidirectional"))
    )
    (net (code "180") (name "/Ver_AD9910") (class "Default")
      (node (ref "R148") (pin "1") (pinfunction "1_1") (pintype "passive"))
      (node (ref "R149") (pin "2") (pinfunction "2_2") (pintype "passive"))
      (node (ref "U1") (pin "T3") (pinfunction "IOB_61_T3") (pintype "bidirectional"))
    )
    (net (code "185") (name "GND") (class "Default")
      (node (ref "C85") (pin "1") (pinfunction "1_1") (pintype "passive"))
      (node (ref "OSC3") (pin "2") (pinfunction "GND_2") (pintype "power_in"))
      (node (ref "R142") (pin "1") (pinfunction "1_1") (pintype "passive"))
      (node (ref "R144") (pin "1") (pinfunction "1_1") (pintype "passive"))
      (node (ref "R146") (pin "1") (pinfunction "1_1") (pintype "passive"))
      (node (ref "R149") (pin "1") (pinfunction "1_1") (pintype "passive"))
      (node (ref "R172") (pin "1") (pinfunction "1_1") (pintype "passive"))
      (node (ref "R174") (pin "1") (pinfunction "1_1") (pintype "passive"))
      (node (ref "R175") (pin "1") (pinfunction "1_1") (pintype "passive"))
    )
    (net (code "186") (name "Net-(OSC3-OUT)") (class "Default")
      (node (ref "OSC3") (pin "3") (pinfunction "OUT_3") (pintype "output"))
      (node (ref "R351") (pin "1") (pinfunction "1_1") (pintype "passive"))
    )
    (net (code "187") (name "P3V3") (class "Default")
      (node (ref "C85") (pin "2") (pinfunction "2_2") (pintype "passive"))
      (node (ref "OSC3") (pin "1") (pinfunction "E_1") (pintype "input"))
      (node (ref "OSC3") (pin "4") (pinfunction "+Vs_4") (pintype "power_in"))
      (node (ref "R148") (pin "2") (pinfunction "2_2") (pintype "passive"))
      (node (ref "R171") (pin "1") (pinfunction "1_1") (pintype "passive"))
      (node (ref "R173") (pin "1") (pinfunction "1_1") (pintype "passive"))
      (node (ref "SW1") (pin "1") (pinfunction "1_1") (pintype "bidirectional"))
      (node (ref "SW1") (pin "2") (pinfunction "2_2") (pintype "bidirectional"))
      (node (ref "SW1") (pin "3") (pinfunction "3_3") (pintype "bidirectional"))
      (node (ref "SW1") (pin "4") (pinfunction "4_4") (pintype "bidirectional"))
    )
  )
)
